# Power_Supply.net
KiCad netlist of a schematic drawn in Altium Designer
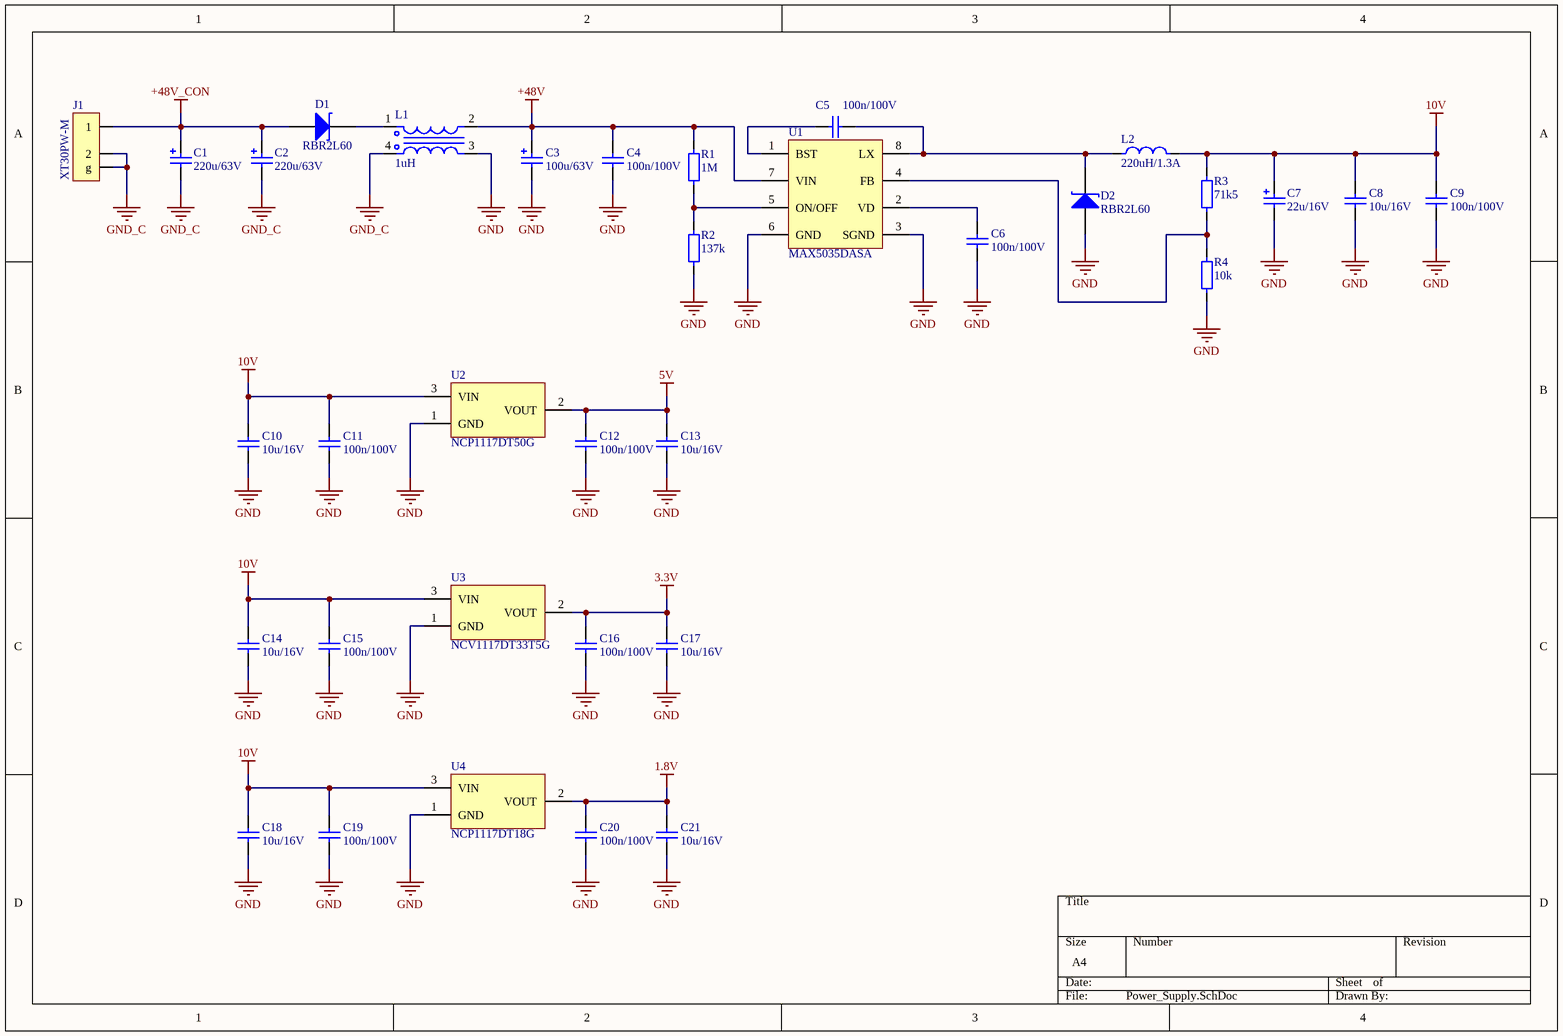
[diagram p0: Power_Supply.SchDoc]

(export (version "E")
  (design (tool "Eeschema 10.0.6"))
  (components
    (comp (ref "C1")
      (value "220u/63V")
      (footprint "CAP_POL_10x20")
      (description "Aluminum Electrolytic Capacitors - Radial Leaded 220uF 63V 20% Radial")
      (fields (field (name "MANUFACTURER") "Murata") (field (name "PART NUMBER") "GRM31CR61A107ME05L"))
      (libsource (lib "CAPACITOR") (part "CAP_POL/220u/63V"))
    )
    (comp (ref "C2")
      (value "220u/63V")
      (footprint "CAP_POL_10x20")
      (description "Aluminum Electrolytic Capacitors - Radial Leaded 220uF 63V 20% Radial")
      (fields (field (name "MANUFACTURER") "Murata") (field (name "PART NUMBER") "GRM31CR61A107ME05L"))
      (libsource (lib "CAPACITOR") (part "CAP_POL/220u/63V"))
    )
    (comp (ref "C3")
      (value "100u/63V")
      (footprint "CAP_POL_10x12")
      (description "Aluminum Electrolytic Capacitors - Radial Leaded WCAP-ATUL 100uF 63V 20% Radial")
      (fields (field (name "MANUFACTURER") "Murata") (field (name "PART NUMBER") "GRM31CR61A107ME05L"))
      (libsource (lib "CAPACITOR") (part "CAP_POL/100u/63V"))
    )
    (comp (ref "C4")
      (value "100n/100V")
      (footprint "CAP_0805N")
      (description "Multilayer Ceramic Capacitors MLCC - SMD/SMT 100V 0.1uF X7R 0805 10%")
      (fields (field (name "MANUFACTURER") "KEMET") (field (name "PART NUMBER") "C0805C104J5RACTU"))
      (libsource (lib "CAPACITOR") (part "CAP_MLCC/100n/100V/0805"))
    )
    (comp (ref "C5")
      (value "100n/100V")
      (footprint "CAP_0805N")
      (description "Multilayer Ceramic Capacitors MLCC - SMD/SMT 100V 0.1uF X7R 0805 10%")
      (fields (field (name "MANUFACTURER") "KEMET") (field (name "PART NUMBER") "C0805C104J5RACTU"))
      (libsource (lib "CAPACITOR") (part "CAP_MLCC/100n/100V/0805"))
    )
    (comp (ref "C6")
      (value "100n/100V")
      (footprint "CAP_0805N")
      (description "Multilayer Ceramic Capacitors MLCC - SMD/SMT 100V 0.1uF X7R 0805 10%")
      (fields (field (name "MANUFACTURER") "KEMET") (field (name "PART NUMBER") "C0805C104J5RACTU"))
      (libsource (lib "CAPACITOR") (part "CAP_MLCC/100n/100V/0805"))
    )
    (comp (ref "C7")
      (value "22u/16V")
      (footprint "CAPCP3528X20N")
      (description "Tantalum Capacitors - Solid SMD 22uF 16V 10% L ESR")
      (fields (field (name "MANUFACTURER") "Murata") (field (name "PART NUMBER") "GRM31CR61A107ME05L"))
      (libsource (lib "CAPACITOR") (part "CAP_POL/22u/16V"))
    )
    (comp (ref "C8")
      (value "10u/16V")
      (footprint "CAP_0805N")
      (description "Multilayer Ceramic Capacitors MLCC - SMD/SMT 10UF 16V 10% 0805")
      (fields (field (name "MANUFACTURER") "Murata") (field (name "PART NUMBER") "C0805C106K8PACTU"))
      (libsource (lib "CAPACITOR") (part "CAP_MLCC/10u/16V/0805"))
    )
    (comp (ref "C9")
      (value "100n/100V")
      (footprint "CAP_0805N")
      (description "Multilayer Ceramic Capacitors MLCC - SMD/SMT 100V 0.1uF X7R 0805 10%")
      (fields (field (name "MANUFACTURER") "KEMET") (field (name "PART NUMBER") "C0805C104J5RACTU"))
      (libsource (lib "CAPACITOR") (part "CAP_MLCC/100n/100V/0805"))
    )
    (comp (ref "C10")
      (value "10u/16V")
      (footprint "CAP_0805N")
      (description "Multilayer Ceramic Capacitors MLCC - SMD/SMT 10UF 16V 10% 0805")
      (fields (field (name "MANUFACTURER") "Murata") (field (name "PART NUMBER") "C0805C106K8PACTU"))
      (libsource (lib "CAPACITOR") (part "CAP_MLCC/10u/16V/0805"))
    )
    (comp (ref "C11")
      (value "100n/100V")
      (footprint "CAP_0805N")
      (description "Multilayer Ceramic Capacitors MLCC - SMD/SMT 100V 0.1uF X7R 0805 10%")
      (fields (field (name "MANUFACTURER") "KEMET") (field (name "PART NUMBER") "C0805C104J5RACTU"))
      (libsource (lib "CAPACITOR") (part "CAP_MLCC/100n/100V/0805"))
    )
    (comp (ref "C12")
      (value "100n/100V")
      (footprint "CAP_0805N")
      (description "Multilayer Ceramic Capacitors MLCC - SMD/SMT 100V 0.1uF X7R 0805 10%")
      (fields (field (name "MANUFACTURER") "KEMET") (field (name "PART NUMBER") "C0805C104J5RACTU"))
      (libsource (lib "CAPACITOR") (part "CAP_MLCC/100n/100V/0805"))
    )
    (comp (ref "C13")
      (value "10u/16V")
      (footprint "CAP_0805N")
      (description "Multilayer Ceramic Capacitors MLCC - SMD/SMT 10UF 16V 10% 0805")
      (fields (field (name "MANUFACTURER") "Murata") (field (name "PART NUMBER") "C0805C106K8PACTU"))
      (libsource (lib "CAPACITOR") (part "CAP_MLCC/10u/16V/0805"))
    )
    (comp (ref "C14")
      (value "10u/16V")
      (footprint "CAP_0805N")
      (description "Multilayer Ceramic Capacitors MLCC - SMD/SMT 10UF 16V 10% 0805")
      (fields (field (name "MANUFACTURER") "Murata") (field (name "PART NUMBER") "C0805C106K8PACTU"))
      (libsource (lib "CAPACITOR") (part "CAP_MLCC/10u/16V/0805"))
    )
    (comp (ref "C15")
      (value "100n/100V")
      (footprint "CAP_0805N")
      (description "Multilayer Ceramic Capacitors MLCC - SMD/SMT 100V 0.1uF X7R 0805 10%")
      (fields (field (name "MANUFACTURER") "KEMET") (field (name "PART NUMBER") "C0805C104J5RACTU"))
      (libsource (lib "CAPACITOR") (part "CAP_MLCC/100n/100V/0805"))
    )
    (comp (ref "C16")
      (value "100n/100V")
      (footprint "CAP_0805N")
      (description "Multilayer Ceramic Capacitors MLCC - SMD/SMT 100V 0.1uF X7R 0805 10%")
      (fields (field (name "MANUFACTURER") "KEMET") (field (name "PART NUMBER") "C0805C104J5RACTU"))
      (libsource (lib "CAPACITOR") (part "CAP_MLCC/100n/100V/0805"))
    )
    (comp (ref "C17")
      (value "10u/16V")
      (footprint "CAP_0805N")
      (description "Multilayer Ceramic Capacitors MLCC - SMD/SMT 10UF 16V 10% 0805")
      (fields (field (name "MANUFACTURER") "Murata") (field (name "PART NUMBER") "C0805C106K8PACTU"))
      (libsource (lib "CAPACITOR") (part "CAP_MLCC/10u/16V/0805"))
    )
    (comp (ref "C18")
      (value "10u/16V")
      (footprint "CAP_0805N")
      (description "Multilayer Ceramic Capacitors MLCC - SMD/SMT 10UF 16V 10% 0805")
      (fields (field (name "MANUFACTURER") "Murata") (field (name "PART NUMBER") "C0805C106K8PACTU"))
      (libsource (lib "CAPACITOR") (part "CAP_MLCC/10u/16V/0805"))
    )
    (comp (ref "C19")
      (value "100n/100V")
      (footprint "CAP_0805N")
      (description "Multilayer Ceramic Capacitors MLCC - SMD/SMT 100V 0.1uF X7R 0805 10%")
      (fields (field (name "MANUFACTURER") "KEMET") (field (name "PART NUMBER") "C0805C104J5RACTU"))
      (libsource (lib "CAPACITOR") (part "CAP_MLCC/100n/100V/0805"))
    )
    (comp (ref "C20")
      (value "100n/100V")
      (footprint "CAP_0805N")
      (description "Multilayer Ceramic Capacitors MLCC - SMD/SMT 100V 0.1uF X7R 0805 10%")
      (fields (field (name "MANUFACTURER") "KEMET") (field (name "PART NUMBER") "C0805C104J5RACTU"))
      (libsource (lib "CAPACITOR") (part "CAP_MLCC/100n/100V/0805"))
    )
    (comp (ref "C21")
      (value "10u/16V")
      (footprint "CAP_0805N")
      (description "Multilayer Ceramic Capacitors MLCC - SMD/SMT 10UF 16V 10% 0805")
      (fields (field (name "MANUFACTURER") "Murata") (field (name "PART NUMBER") "C0805C106K8PACTU"))
      (libsource (lib "CAPACITOR") (part "CAP_MLCC/10u/16V/0805"))
    )
    (comp (ref "D1")
      (value "RBR2L60")
      (footprint "DO-214AC")
      (description "Schottky Diodes & Rectifiers SCHOTTKY BARRIER DIODE")
      (fields
        (field (name "MANUFACTURER") "ROHM Semiconductor")
        (field (name "PART NUMBER") "RBR2L60ADDTE25")
      )
      (libsource (lib "DIODE") (part "RBR2L60"))
    )
    (comp (ref "D2")
      (value "RBR2L60")
      (footprint "DO-214AC")
      (description "Schottky Diodes & Rectifiers SCHOTTKY BARRIER DIODE")
      (fields
        (field (name "MANUFACTURER") "ROHM Semiconductor")
        (field (name "PART NUMBER") "RBR2L60ADDTE25")
      )
      (libsource (lib "DIODE") (part "RBR2L60"))
    )
    (comp (ref "J1")
      (value "XT30PW-M")
      (footprint "XT30_PCB")
      (description "Gniazdo; zasilające DC; XT30; męskie; PIN: 2; na PCB; THT; 15A; 500V")
      (libsource (lib "CONNECTOR") (part "XT30_PCB"))
    )
    (comp (ref "L1")
      (value "1uH")
      (footprint "744235601")
      (description "Common Mode Chokes / Filters WE-CNSW 1812 1200mA 1uH 100kHz AECQ200")
      (fields (field (name "MANUFACTURER") "Würth Elektronik") (field (name "PART NUMBER") "744282010"))
      (libsource (lib "INDUCTOR") (part "CMC_744235601"))
    )
    (comp (ref "L2")
      (value "220uH/1.3A")
      (footprint "INDP125125X65N")
      (description "Fixed Inductors 220uH 10% SMD 1260")
      (fields (field (name "MANUFACTURER") "Bourns") (field (name "PART NUMBER") "SRR1260-221K"))
      (libsource (lib "INDUCTOR") (part "SRR1260-221K"))
    )
    (comp (ref "R1")
      (value "1M")
      (footprint "RES_0805N")
      (description "Thick Film Resistors - SMD .125watt 1Mohms 1% 0805 100ppm")
      (fields (field (name "MANUFACTURER") "Vishay") (field (name "PART NUMBER") "CRCW080510R0FKEAC"))
      (libsource (lib "RESISTOR") (part "RES/1M/1%/0805"))
    )
    (comp (ref "R2")
      (value "137k")
      (footprint "RES_0805N")
      (description "Thick Film Resistors - SMD 1/8Watt 137kohms 1% Commercial Use")
      (fields (field (name "MANUFACTURER") "Vishay") (field (name "PART NUMBER") "CRCW080510R0FKEAC"))
      (libsource (lib "RESISTOR") (part "RES/137k/1%/0805"))
    )
    (comp (ref "R3")
      (value "71k5")
      (footprint "RES_0805N")
      (description "Thick Film Resistors - SMD 1/8Watt 137kohms 1% Commercial Use")
      (fields (field (name "MANUFACTURER") "Vishay") (field (name "PART NUMBER") "CRCW080510R0FKEAC"))
      (libsource (lib "RESISTOR") (part "RES/137k/1%/0805"))
    )
    (comp (ref "R4")
      (value "10k")
      (footprint "RES_0805N")
      (description "Thick Film Resistors - SMD 1/8Watt 137kohms 1% Commercial Use")
      (fields (field (name "MANUFACTURER") "Vishay") (field (name "PART NUMBER") "CRCW080510R0FKEAC"))
      (libsource (lib "RESISTOR") (part "RES/137k/1%/0805"))
    )
    (comp (ref "U1")
      (value "MAX5035DASA")
      (footprint "SOIC-8")
      (fields (field (name "MANUFACTURER") "Maxim Integrated") (field (name "PART NUMBER") "MAX5035DASA+"))
      (libsource (lib "IC") (part "MAX5035DASA"))
    )
    (comp (ref "U2")
      (value "NCP1117DT50G")
      (footprint "NCP1117DT50G")
      (description "NCP1117DT50G\r\n\r\nLDO 5V 1A")
      (libsource (lib "IC") (part "NCP1117DT50G"))
    )
    (comp (ref "U3")
      (value "NCV1117DT33T5G")
      (footprint "NCV1117DT33T5G")
      (description "LDO 3.3V\r\n\r\nNCV1117DT33T5G")
      (libsource (lib "IC") (part "NCV1117DT33T5G"))
    )
    (comp (ref "U4")
      (value "NCP1117DT18G")
      (footprint "NCV1117DT33T5G")
      (description "NCP1117DT18RKG\r\n\r\nLDO 1,8V 1A")
      (libsource (lib "IC") (part "NCP1117DT18RKG"))
    )
  )
  (nets
    (net (code "1") (name "+48V") (class "Default")
      (node (ref "C3") (pin "2") (pinfunction "2_2") (pintype "passive"))
      (node (ref "C4") (pin "2") (pinfunction "2_2") (pintype "passive"))
      (node (ref "L1") (pin "2") (pinfunction "2_2") (pintype "passive"))
      (node (ref "R1") (pin "2") (pinfunction "2_2") (pintype "passive"))
      (node (ref "U1") (pin "7") (pinfunction "VIN_7") (pintype "passive"))
    )
    (net (code "2") (name "+48V_CON") (class "Default")
      (node (ref "C1") (pin "2") (pinfunction "2_2") (pintype "passive"))
      (node (ref "C2") (pin "2") (pinfunction "2_2") (pintype "passive"))
      (node (ref "D1") (pin "1") (pinfunction "A_1") (pintype "passive"))
      (node (ref "J1") (pin "1") (pinfunction "1_1") (pintype "passive"))
    )
    (net (code "3") (name "1.8V") (class "Default")
      (node (ref "C20") (pin "2") (pinfunction "2_2") (pintype "passive"))
      (node (ref "C21") (pin "2") (pinfunction "2_2") (pintype "passive"))
      (node (ref "U4") (pin "2") (pinfunction "VOUT_2") (pintype "passive"))
    )
    (net (code "4") (name "3.3V") (class "Default")
      (node (ref "C16") (pin "2") (pinfunction "2_2") (pintype "passive"))
      (node (ref "C17") (pin "2") (pinfunction "2_2") (pintype "passive"))
      (node (ref "U3") (pin "2") (pinfunction "VOUT_2") (pintype "passive"))
    )
    (net (code "5") (name "5V") (class "Default")
      (node (ref "C12") (pin "2") (pinfunction "2_2") (pintype "passive"))
      (node (ref "C13") (pin "2") (pinfunction "2_2") (pintype "passive"))
      (node (ref "U2") (pin "2") (pinfunction "VOUT_2") (pintype "passive"))
    )
    (net (code "6") (name "10V") (class "Default")
      (node (ref "C10") (pin "2") (pinfunction "2_2") (pintype "passive"))
      (node (ref "C11") (pin "2") (pinfunction "2_2") (pintype "passive"))
      (node (ref "C14") (pin "2") (pinfunction "2_2") (pintype "passive"))
      (node (ref "C15") (pin "2") (pinfunction "2_2") (pintype "passive"))
      (node (ref "C18") (pin "2") (pinfunction "2_2") (pintype "passive"))
      (node (ref "C19") (pin "2") (pinfunction "2_2") (pintype "passive"))
      (node (ref "C7") (pin "2") (pinfunction "2_2") (pintype "passive"))
      (node (ref "C8") (pin "2") (pinfunction "2_2") (pintype "passive"))
      (node (ref "C9") (pin "2") (pinfunction "2_2") (pintype "passive"))
      (node (ref "L2") (pin "2") (pinfunction "2_2") (pintype "passive"))
      (node (ref "R3") (pin "2") (pinfunction "2_2") (pintype "passive"))
      (node (ref "U2") (pin "3") (pinfunction "VIN_3") (pintype "passive"))
      (node (ref "U3") (pin "3") (pinfunction "VIN_3") (pintype "passive"))
      (node (ref "U4") (pin "3") (pinfunction "VIN_3") (pintype "passive"))
    )
    (net (code "7") (name "GND") (class "Default")
      (node (ref "C10") (pin "1") (pinfunction "1_1") (pintype "passive"))
      (node (ref "C11") (pin "1") (pinfunction "1_1") (pintype "passive"))
      (node (ref "C12") (pin "1") (pinfunction "1_1") (pintype "passive"))
      (node (ref "C13") (pin "1") (pinfunction "1_1") (pintype "passive"))
      (node (ref "C14") (pin "1") (pinfunction "1_1") (pintype "passive"))
      (node (ref "C15") (pin "1") (pinfunction "1_1") (pintype "passive"))
      (node (ref "C16") (pin "1") (pinfunction "1_1") (pintype "passive"))
      (node (ref "C17") (pin "1") (pinfunction "1_1") (pintype "passive"))
      (node (ref "C18") (pin "1") (pinfunction "1_1") (pintype "passive"))
      (node (ref "C19") (pin "1") (pinfunction "1_1") (pintype "passive"))
      (node (ref "C20") (pin "1") (pinfunction "1_1") (pintype "passive"))
      (node (ref "C21") (pin "1") (pinfunction "1_1") (pintype "passive"))
      (node (ref "C3") (pin "1") (pinfunction "1_1") (pintype "passive"))
      (node (ref "C4") (pin "1") (pinfunction "1_1") (pintype "passive"))
      (node (ref "C6") (pin "1") (pinfunction "1_1") (pintype "passive"))
      (node (ref "C7") (pin "1") (pinfunction "1_1") (pintype "passive"))
      (node (ref "C8") (pin "1") (pinfunction "1_1") (pintype "passive"))
      (node (ref "C9") (pin "1") (pinfunction "1_1") (pintype "passive"))
      (node (ref "D2") (pin "1") (pinfunction "A_1") (pintype "passive"))
      (node (ref "L1") (pin "3") (pinfunction "3_3") (pintype "passive"))
      (node (ref "R2") (pin "1") (pinfunction "1_1") (pintype "passive"))
      (node (ref "R4") (pin "1") (pinfunction "1_1") (pintype "passive"))
      (node (ref "U1") (pin "3") (pinfunction "SGND_3") (pintype "passive"))
      (node (ref "U1") (pin "6") (pinfunction "GND_6") (pintype "passive"))
      (node (ref "U2") (pin "1") (pinfunction "GND_1") (pintype "passive"))
      (node (ref "U3") (pin "1") (pinfunction "GND_1") (pintype "passive"))
      (node (ref "U4") (pin "1") (pinfunction "GND_1") (pintype "passive"))
    )
    (net (code "8") (name "GND_C") (class "Default")
      (node (ref "C1") (pin "1") (pinfunction "1_1") (pintype "passive"))
      (node (ref "C2") (pin "1") (pinfunction "1_1") (pintype "passive"))
      (node (ref "J1") (pin "2") (pinfunction "2_2") (pintype "passive"))
      (node (ref "J1") (pin "g") (pinfunction "g_g") (pintype "passive"))
      (node (ref "L1") (pin "4") (pinfunction "4_4") (pintype "passive"))
    )
    (net (code "9") (name "Net-(D1-K)") (class "Default")
      (node (ref "D1") (pin "2") (pinfunction "K_2") (pintype "passive"))
      (node (ref "L1") (pin "1") (pinfunction "1_1") (pintype "passive"))
    )
    (net (code "10") (name "Net-(D2-K)") (class "Default")
      (node (ref "C5") (pin "1") (pinfunction "1_1") (pintype "passive"))
      (node (ref "D2") (pin "2") (pinfunction "K_2") (pintype "passive"))
      (node (ref "L2") (pin "1") (pinfunction "1_1") (pintype "passive"))
      (node (ref "U1") (pin "8") (pinfunction "LX_8") (pintype "passive"))
    )
    (net (code "11") (name "Net-(U1-BST)") (class "Default")
      (node (ref "C5") (pin "2") (pinfunction "2_2") (pintype "passive"))
      (node (ref "U1") (pin "1") (pinfunction "BST_1") (pintype "passive"))
    )
    (net (code "12") (name "Net-(U1-FB)") (class "Default")
      (node (ref "R3") (pin "1") (pinfunction "1_1") (pintype "passive"))
      (node (ref "R4") (pin "2") (pinfunction "2_2") (pintype "passive"))
      (node (ref "U1") (pin "4") (pinfunction "FB_4") (pintype "passive"))
    )
    (net (code "13") (name "Net-(U1-ON{slash}OFF)") (class "Default")
      (node (ref "R1") (pin "1") (pinfunction "1_1") (pintype "passive"))
      (node (ref "R2") (pin "2") (pinfunction "2_2") (pintype "passive"))
      (node (ref "U1") (pin "5") (pinfunction "ON/OFF_5") (pintype "passive"))
    )
    (net (code "14") (name "Net-(U1-VD)") (class "Default")
      (node (ref "C6") (pin "2") (pinfunction "2_2") (pintype "passive"))
      (node (ref "U1") (pin "2") (pinfunction "VD_2") (pintype "passive"))
    )
  )
)
